# isoDebug-Isolation.net
KiCad netlist of a schematic drawn in Altium Designer
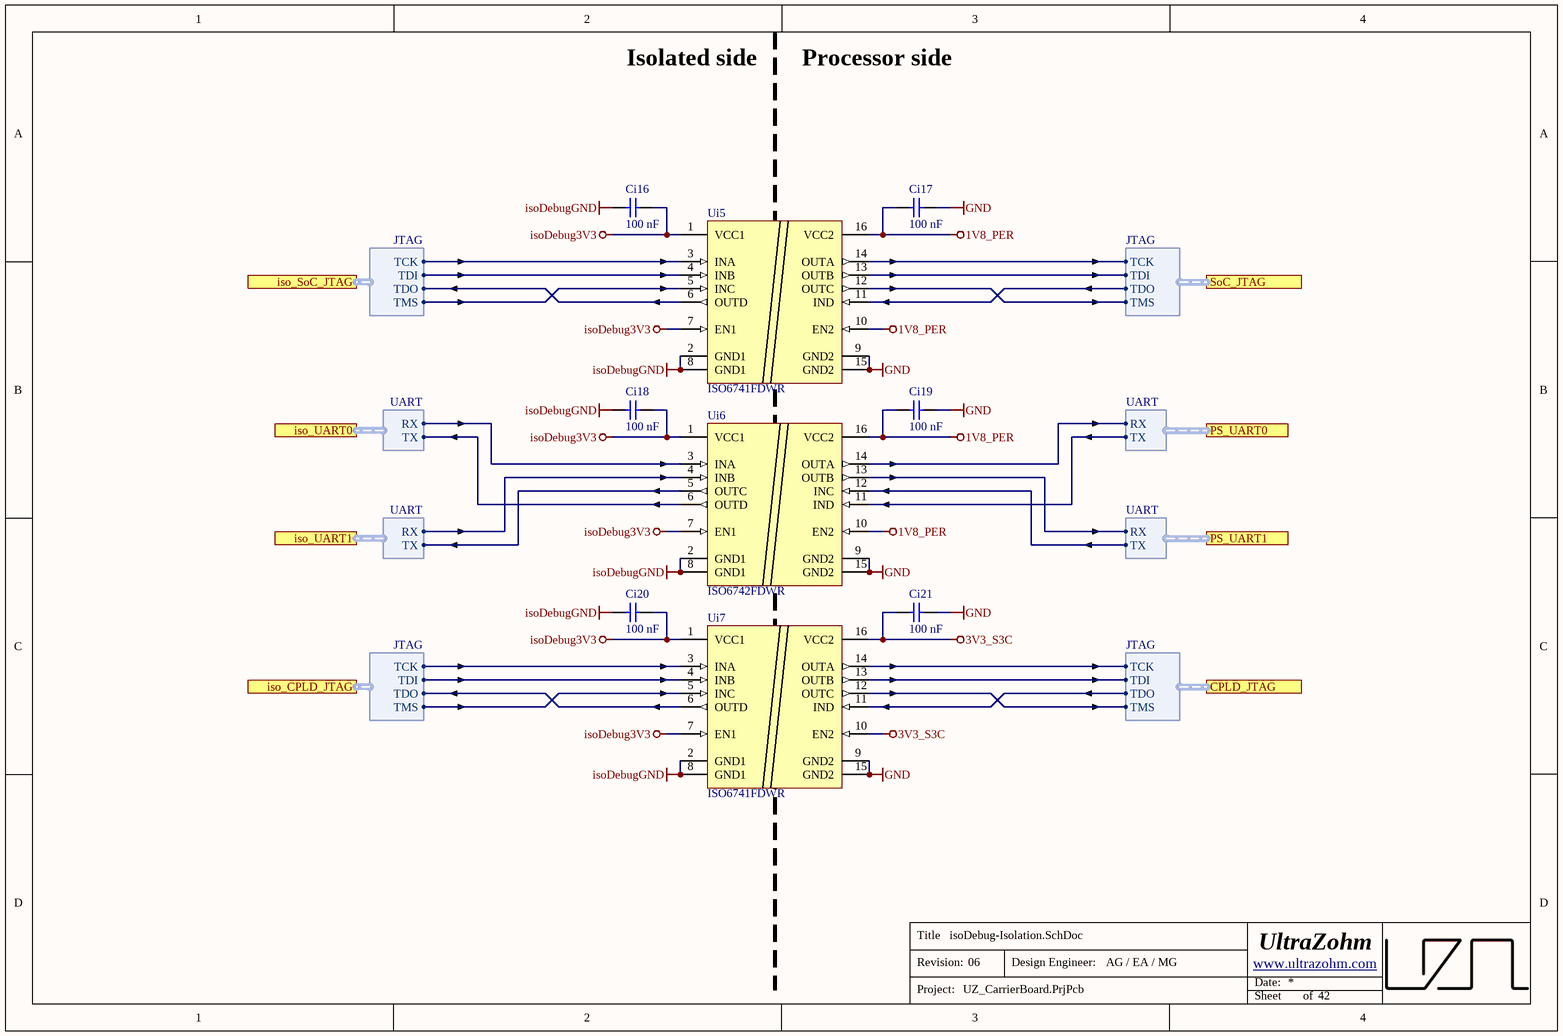
[diagram p0: isoDebug-Isolation.SchDoc]

(export (version "E")
  (design (tool "Eeschema 10.0.6"))
  (components
    (comp (ref "Ci16")
      (value "100 nF")
      (footprint "C_0402_TE")
      (description "Generic capacitor")
      (fields
        (field (name "MANUFACTURER PART NUMBER") "UZgen_C_0402_100nF_50V_X7R")
        (field (name "MANUFACTURER") "UZgen")
        (field (name "CREATED FROM") "UZgenTool")
      )
      (libsource (lib "user") (part "CAP-NP"))
    )
    (comp (ref "Ci17")
      (value "100 nF")
      (footprint "C_0402_TE")
      (description "Generic capacitor")
      (fields
        (field (name "MANUFACTURER PART NUMBER") "UZgen_C_0402_100nF_50V_X7R")
        (field (name "MANUFACTURER") "UZgen")
        (field (name "CREATED FROM") "UZgenTool")
      )
      (libsource (lib "user") (part "CAP-NP"))
    )
    (comp (ref "Ci18")
      (value "100 nF")
      (footprint "C_0402_TE")
      (description "Generic capacitor")
      (fields
        (field (name "MANUFACTURER PART NUMBER") "UZgen_C_0402_100nF_50V_X7R")
        (field (name "MANUFACTURER") "UZgen")
        (field (name "CREATED FROM") "UZgenTool")
      )
      (libsource (lib "user") (part "CAP-NP"))
    )
    (comp (ref "Ci19")
      (value "100 nF")
      (footprint "C_0402_TE")
      (description "Generic capacitor")
      (fields
        (field (name "MANUFACTURER PART NUMBER") "UZgen_C_0402_100nF_50V_X7R")
        (field (name "MANUFACTURER") "UZgen")
        (field (name "CREATED FROM") "UZgenTool")
      )
      (libsource (lib "user") (part "CAP-NP"))
    )
    (comp (ref "Ci20")
      (value "100 nF")
      (footprint "C_0402_TE")
      (description "Generic capacitor")
      (fields
        (field (name "MANUFACTURER PART NUMBER") "UZgen_C_0402_100nF_50V_X7R")
        (field (name "MANUFACTURER") "UZgen")
        (field (name "CREATED FROM") "UZgenTool")
      )
      (libsource (lib "user") (part "CAP-NP"))
    )
    (comp (ref "Ci21")
      (value "100 nF")
      (footprint "C_0402_TE")
      (description "Generic capacitor")
      (fields
        (field (name "MANUFACTURER PART NUMBER") "UZgen_C_0402_100nF_50V_X7R")
        (field (name "MANUFACTURER") "UZgen")
        (field (name "CREATED FROM") "UZgenTool")
      )
      (libsource (lib "user") (part "CAP-NP"))
    )
    (comp (ref "Ui5")
      (value "ISO6741FDWR")
      (footprint "SOIC127P1030X265-16N")
      (description "Digital Isolators General-purpose, quad-channel, 3/1 digital isolator 16-SOIC -40 to 125")
      (fields
        (field (name "MANUFACTURER") "Texas Instruments")
        (field (name "LCSC PART NUMBER") "C5216433")
        (field (name "CREATED FROM") "FRosner")
      )
      (libsource (lib "user") (part "ISO6741"))
    )
    (comp (ref "Ui6")
      (value "ISO6742FDWR")
      (footprint "SOIC127P1030X265-16N")
      (description "Digital Isolators General-purpose, quad-channel, 2/2 digital isolator")
      (fields
        (field (name "MANUFACTURER") "Texas Instruments")
        (field (name "LCSC PART NUMBER") "C5216408")
        (field (name "CREATED FROM") "FRosner")
      )
      (libsource (lib "user") (part "ISO6742"))
    )
    (comp (ref "Ui7")
      (value "ISO6741FDWR")
      (footprint "SOIC127P1030X265-16N")
      (description "Digital Isolators General-purpose, quad-channel, 3/1 digital isolator 16-SOIC -40 to 125")
      (fields
        (field (name "MANUFACTURER") "Texas Instruments")
        (field (name "LCSC PART NUMBER") "C5216433")
        (field (name "CREATED FROM") "FRosner")
      )
      (libsource (lib "user") (part "ISO6741"))
    )
  )
  (nets
    (net (code "5") (name "1V8_PER") (class "Default")
      (node (ref "Ci17") (pin "2") (pinfunction "2_2") (pintype "passive"))
      (node (ref "Ci19") (pin "2") (pinfunction "2_2") (pintype "passive"))
      (node (ref "Ui5") (pin "10") (pinfunction "EN2_10") (pintype "input"))
      (node (ref "Ui5") (pin "16") (pinfunction "VCC2_16") (pintype "power_in"))
      (node (ref "Ui6") (pin "10") (pinfunction "EN2_10") (pintype "input"))
      (node (ref "Ui6") (pin "16") (pinfunction "VCC2_16") (pintype "power_in"))
    )
    (net (code "6") (name "3V3_S3C") (class "Default")
      (node (ref "Ci21") (pin "2") (pinfunction "2_2") (pintype "passive"))
      (node (ref "Ui7") (pin "10") (pinfunction "EN2_10") (pintype "input"))
      (node (ref "Ui7") (pin "16") (pinfunction "VCC2_16") (pintype "power_in"))
    )
    (net (code "7") (name "GND") (class "Default")
      (node (ref "Ci17") (pin "1") (pinfunction "1_1") (pintype "passive"))
      (node (ref "Ci19") (pin "1") (pinfunction "1_1") (pintype "passive"))
      (node (ref "Ci21") (pin "1") (pinfunction "1_1") (pintype "passive"))
      (node (ref "Ui5") (pin "15") (pinfunction "GND2_15") (pintype "power_in"))
      (node (ref "Ui5") (pin "9") (pinfunction "GND2_9") (pintype "power_in"))
      (node (ref "Ui6") (pin "15") (pinfunction "GND2_15") (pintype "power_in"))
      (node (ref "Ui6") (pin "9") (pinfunction "GND2_9") (pintype "power_in"))
      (node (ref "Ui7") (pin "15") (pinfunction "GND2_15") (pintype "power_in"))
      (node (ref "Ui7") (pin "9") (pinfunction "GND2_9") (pintype "power_in"))
    )
    (net (code "8") (name "isoDebug3V3") (class "Default")
      (node (ref "Ci16") (pin "1") (pinfunction "1_1") (pintype "passive"))
      (node (ref "Ci18") (pin "1") (pinfunction "1_1") (pintype "passive"))
      (node (ref "Ci20") (pin "1") (pinfunction "1_1") (pintype "passive"))
      (node (ref "Ui5") (pin "1") (pinfunction "VCC1_1") (pintype "power_in"))
      (node (ref "Ui5") (pin "7") (pinfunction "EN1_7") (pintype "input"))
      (node (ref "Ui6") (pin "1") (pinfunction "VCC1_1") (pintype "power_in"))
      (node (ref "Ui6") (pin "7") (pinfunction "EN1_7") (pintype "input"))
      (node (ref "Ui7") (pin "1") (pinfunction "VCC1_1") (pintype "power_in"))
      (node (ref "Ui7") (pin "7") (pinfunction "EN1_7") (pintype "input"))
    )
    (net (code "9") (name "isoDebugGND") (class "Default")
      (node (ref "Ci16") (pin "2") (pinfunction "2_2") (pintype "passive"))
      (node (ref "Ci18") (pin "2") (pinfunction "2_2") (pintype "passive"))
      (node (ref "Ci20") (pin "2") (pinfunction "2_2") (pintype "passive"))
      (node (ref "Ui5") (pin "2") (pinfunction "GND1_2") (pintype "power_in"))
      (node (ref "Ui5") (pin "8") (pinfunction "GND1_8") (pintype "power_in"))
      (node (ref "Ui6") (pin "2") (pinfunction "GND1_2") (pintype "power_in"))
      (node (ref "Ui6") (pin "8") (pinfunction "GND1_8") (pintype "power_in"))
      (node (ref "Ui7") (pin "2") (pinfunction "GND1_2") (pintype "power_in"))
      (node (ref "Ui7") (pin "8") (pinfunction "GND1_8") (pintype "power_in"))
    )
    (net (code "10") (name "unconnected-(Ui5-INA-Pad3)") (class "Default")
      (node (ref "Ui5") (pin "3") (pinfunction "INA_3") (pintype "input"))
    )
    (net (code "11") (name "unconnected-(Ui5-INB-Pad4)") (class "Default")
      (node (ref "Ui5") (pin "4") (pinfunction "INB_4") (pintype "input"))
    )
    (net (code "12") (name "unconnected-(Ui5-INC-Pad5)") (class "Default")
      (node (ref "Ui5") (pin "5") (pinfunction "INC_5") (pintype "input"))
    )
    (net (code "13") (name "unconnected-(Ui5-IND-Pad11)") (class "Default")
      (node (ref "Ui5") (pin "11") (pinfunction "IND_11") (pintype "input"))
    )
    (net (code "14") (name "unconnected-(Ui5-OUTA-Pad14)") (class "Default")
      (node (ref "Ui5") (pin "14") (pinfunction "OUTA_14") (pintype "output"))
    )
    (net (code "15") (name "unconnected-(Ui5-OUTB-Pad13)") (class "Default")
      (node (ref "Ui5") (pin "13") (pinfunction "OUTB_13") (pintype "output"))
    )
    (net (code "16") (name "unconnected-(Ui5-OUTC-Pad12)") (class "Default")
      (node (ref "Ui5") (pin "12") (pinfunction "OUTC_12") (pintype "output"))
    )
    (net (code "17") (name "unconnected-(Ui5-OUTD-Pad6)") (class "Default")
      (node (ref "Ui5") (pin "6") (pinfunction "OUTD_6") (pintype "output"))
    )
    (net (code "18") (name "unconnected-(Ui6-INA-Pad3)") (class "Default")
      (node (ref "Ui6") (pin "3") (pinfunction "INA_3") (pintype "input"))
    )
    (net (code "19") (name "unconnected-(Ui6-INB-Pad4)") (class "Default")
      (node (ref "Ui6") (pin "4") (pinfunction "INB_4") (pintype "input"))
    )
    (net (code "20") (name "unconnected-(Ui6-INC-Pad12)") (class "Default")
      (node (ref "Ui6") (pin "12") (pinfunction "INC_12") (pintype "input"))
    )
    (net (code "21") (name "unconnected-(Ui6-IND-Pad11)") (class "Default")
      (node (ref "Ui6") (pin "11") (pinfunction "IND_11") (pintype "input"))
    )
    (net (code "22") (name "unconnected-(Ui6-OUTA-Pad14)") (class "Default")
      (node (ref "Ui6") (pin "14") (pinfunction "OUTA_14") (pintype "output"))
    )
    (net (code "23") (name "unconnected-(Ui6-OUTB-Pad13)") (class "Default")
      (node (ref "Ui6") (pin "13") (pinfunction "OUTB_13") (pintype "output"))
    )
    (net (code "24") (name "unconnected-(Ui6-OUTC-Pad5)") (class "Default")
      (node (ref "Ui6") (pin "5") (pinfunction "OUTC_5") (pintype "output"))
    )
    (net (code "25") (name "unconnected-(Ui6-OUTD-Pad6)") (class "Default")
      (node (ref "Ui6") (pin "6") (pinfunction "OUTD_6") (pintype "output"))
    )
    (net (code "26") (name "unconnected-(Ui7-INA-Pad3)") (class "Default")
      (node (ref "Ui7") (pin "3") (pinfunction "INA_3") (pintype "input"))
    )
    (net (code "27") (name "unconnected-(Ui7-INB-Pad4)") (class "Default")
      (node (ref "Ui7") (pin "4") (pinfunction "INB_4") (pintype "input"))
    )
    (net (code "28") (name "unconnected-(Ui7-INC-Pad5)") (class "Default")
      (node (ref "Ui7") (pin "5") (pinfunction "INC_5") (pintype "input"))
    )
    (net (code "29") (name "unconnected-(Ui7-IND-Pad11)") (class "Default")
      (node (ref "Ui7") (pin "11") (pinfunction "IND_11") (pintype "input"))
    )
    (net (code "30") (name "unconnected-(Ui7-OUTA-Pad14)") (class "Default")
      (node (ref "Ui7") (pin "14") (pinfunction "OUTA_14") (pintype "output"))
    )
    (net (code "31") (name "unconnected-(Ui7-OUTB-Pad13)") (class "Default")
      (node (ref "Ui7") (pin "13") (pinfunction "OUTB_13") (pintype "output"))
    )
    (net (code "32") (name "unconnected-(Ui7-OUTC-Pad12)") (class "Default")
      (node (ref "Ui7") (pin "12") (pinfunction "OUTC_12") (pintype "output"))
    )
    (net (code "33") (name "unconnected-(Ui7-OUTD-Pad6)") (class "Default")
      (node (ref "Ui7") (pin "6") (pinfunction "OUTD_6") (pintype "output"))
    )
  )
)
